# Rotary_Phone_Reader.net
KiCad netlist of a schematic drawn in EAGLE
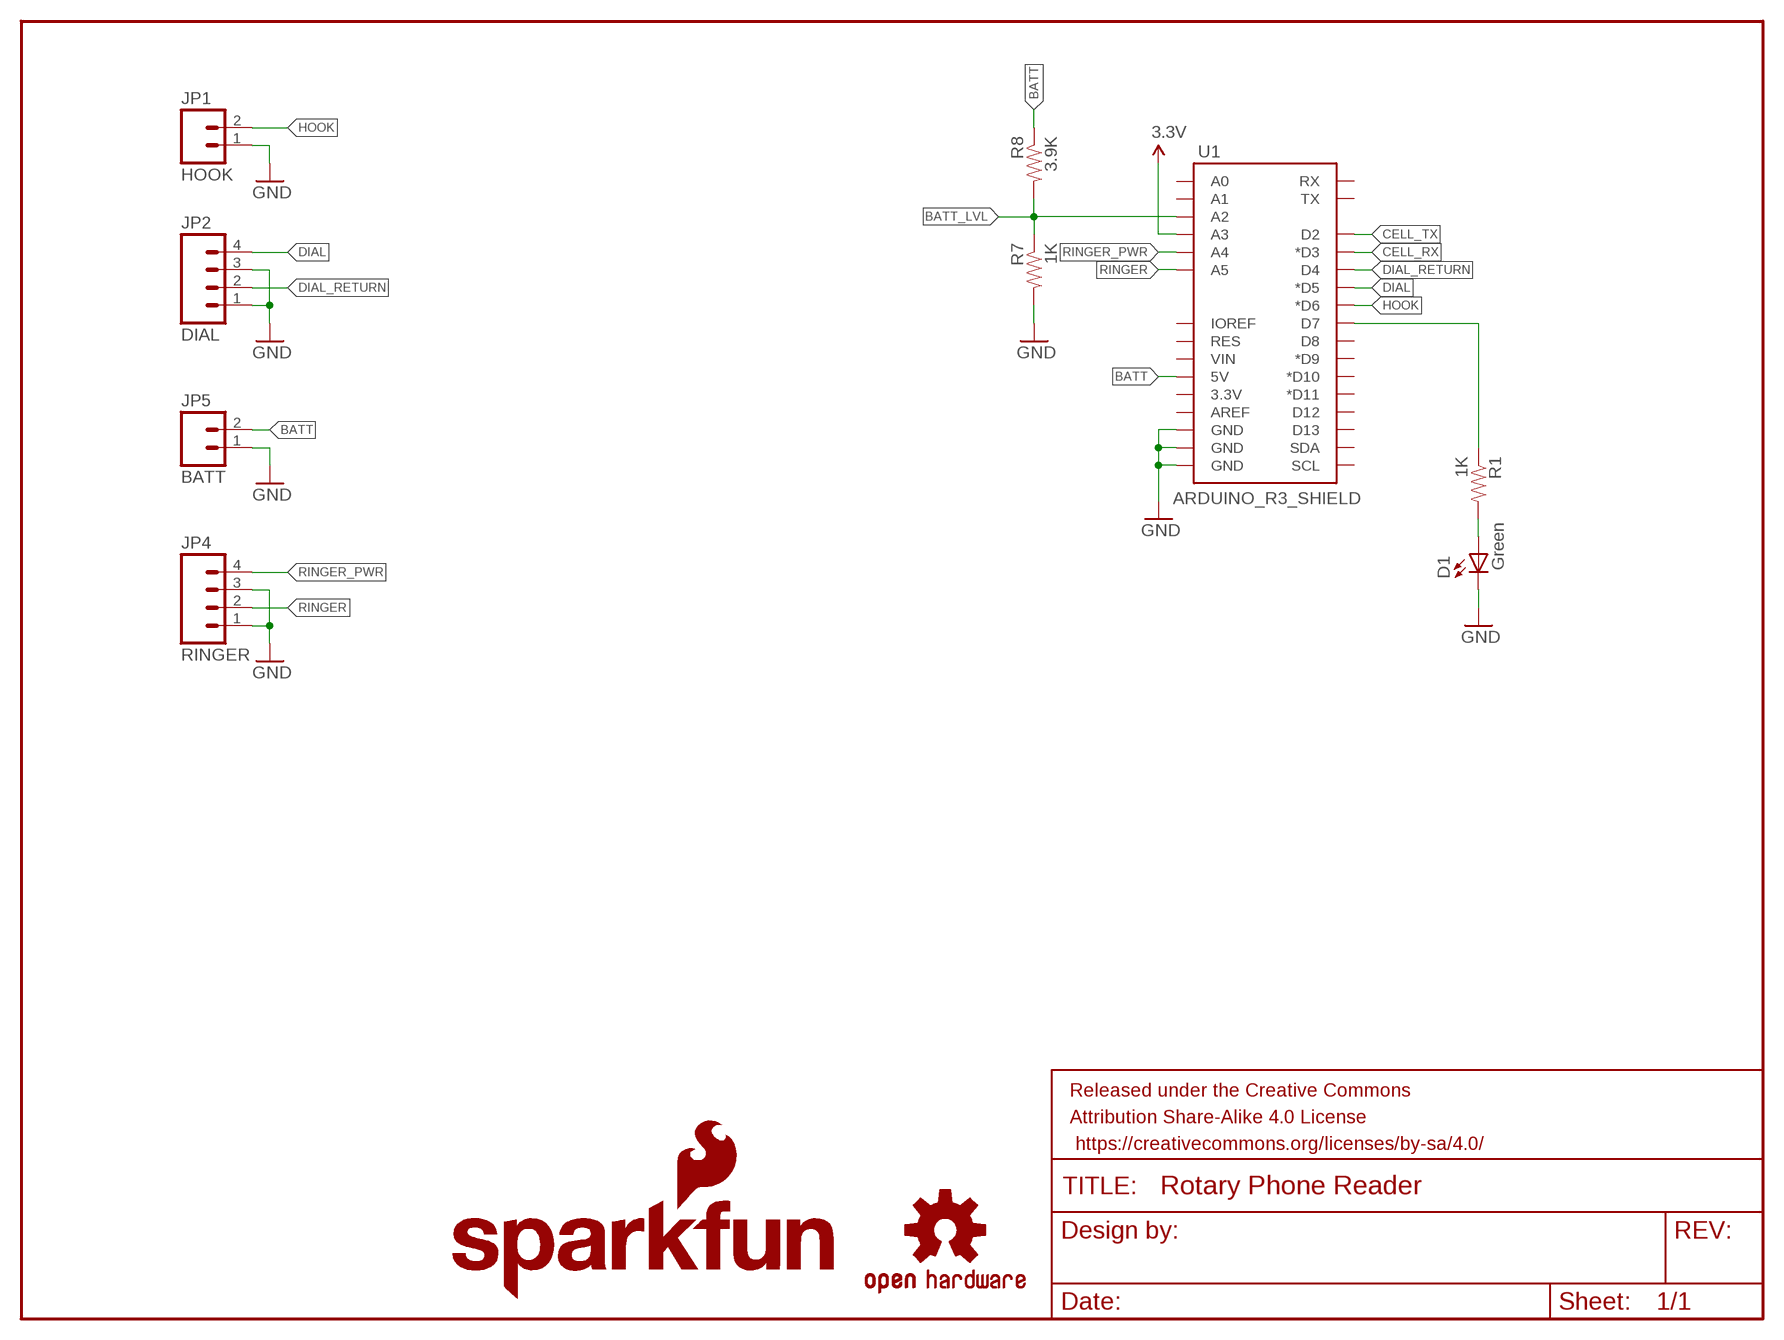
[diagram p0: schematic, sheet 1]

(export (version "E")
  (design (tool "Eeschema 10.0.6"))
  (components
    (comp (ref "D1")
      (value "Green")
      (footprint "eagle-import:LED5MM")
      (libsource (lib "eagle-import") (part "LED5MM"))
    )
    (comp (ref "FRAME1")
      (value "FRAME-LETTER")
      (footprint "eagle-import:CREATIVE_COMMONS")
      (libsource (lib "eagle-import") (part "FRAME-LETTER"))
    )
    (comp (ref "JP1")
      (value "HOOK")
      (footprint "eagle-import:JST-2-PTH")
      (libsource (lib "eagle-import") (part "M02JST-PTH-2"))
    )
    (comp (ref "JP2")
      (value "DIAL")
      (footprint "eagle-import:JST-4-PTH")
      (libsource (lib "eagle-import") (part "M04JST-PTH"))
    )
    (comp (ref "JP4")
      (value "RINGER")
      (footprint "eagle-import:JST-4-PTH")
      (libsource (lib "eagle-import") (part "M04JST-PTH"))
    )
    (comp (ref "JP5")
      (value "BATT")
      (footprint "eagle-import:JST-2-PTH")
      (libsource (lib "eagle-import") (part "M02JST-PTH-2"))
    )
    (comp (ref "LOGO1")
      (value "SFE_LOGO_NAME_FLAME.1_INCH")
      (footprint "eagle-import:SFE_LOGO_NAME_FLAME_.1")
      (libsource (lib "eagle-import") (part "SFE_LOGO_NAME_FLAME.1_INCH"))
    )
    (comp (ref "R1")
      (value "1K")
      (footprint "eagle-import:AXIAL-0.4")
      (libsource (lib "eagle-import") (part "RESISTORPTH-1/4W"))
    )
    (comp (ref "R7")
      (value "1K")
      (footprint "eagle-import:AXIAL-0.4")
      (libsource (lib "eagle-import") (part "RESISTORPTH-1/4W"))
    )
    (comp (ref "R8")
      (value "3.9K")
      (footprint "eagle-import:AXIAL-0.4")
      (libsource (lib "eagle-import") (part "RESISTORPTH-1/4W"))
    )
    (comp (ref "U$7")
      (value "OSHW-LOGOS")
      (footprint "eagle-import:OSHW-LOGO-S")
      (libsource (lib "eagle-import") (part "OSHW-LOGOS"))
    )
    (comp (ref "U1")
      (value "ARDUINO_R3_SHIELD")
      (footprint "eagle-import:UNO_R3_SHIELD")
      (libsource (lib "eagle-import") (part "ARDUINO_R3_SHIELD"))
    )
  )
  (nets
    (net (code "1") (name "3.3V") (class "Default")
      (node (ref "U1") (pin "A3") (pinfunction "A3_A3") (pintype "bidirectional"))
    )
    (net (code "2") (name "BATT") (class "Default")
      (node (ref "JP5") (pin "2") (pinfunction "2_2") (pintype "passive"))
      (node (ref "R8") (pin "P$1") (pinfunction "1_P$1") (pintype "passive"))
      (node (ref "U1") (pin "5V") (pinfunction "5V_5V") (pintype "bidirectional"))
    )
    (net (code "3") (name "BATT_LVL") (class "Default")
      (node (ref "R7") (pin "P$1") (pinfunction "1_P$1") (pintype "passive"))
      (node (ref "R8") (pin "P$2") (pinfunction "2_P$2") (pintype "passive"))
      (node (ref "U1") (pin "A2") (pinfunction "A2_A2") (pintype "bidirectional"))
    )
    (net (code "4") (name "CELL_RX") (class "Default")
      (node (ref "U1") (pin "D3") (pinfunction "*D3_D3") (pintype "bidirectional"))
    )
    (net (code "5") (name "CELL_TX") (class "Default")
      (node (ref "U1") (pin "D2") (pinfunction "D2_D2") (pintype "bidirectional"))
    )
    (net (code "6") (name "DIAL") (class "Default")
      (node (ref "JP2") (pin "4") (pinfunction "4_4") (pintype "passive"))
      (node (ref "U1") (pin "D5") (pinfunction "*D5_D5") (pintype "bidirectional"))
    )
    (net (code "7") (name "DIAL_RETURN") (class "Default")
      (node (ref "JP2") (pin "2") (pinfunction "2_2") (pintype "passive"))
      (node (ref "U1") (pin "D4") (pinfunction "D4_D4") (pintype "bidirectional"))
    )
    (net (code "8") (name "GND") (class "Default")
      (node (ref "D1") (pin "K") (pinfunction "C_K") (pintype "passive"))
      (node (ref "JP1") (pin "1") (pinfunction "1_1") (pintype "passive"))
      (node (ref "JP2") (pin "1") (pinfunction "1_1") (pintype "passive"))
      (node (ref "JP2") (pin "3") (pinfunction "3_3") (pintype "passive"))
      (node (ref "JP4") (pin "1") (pinfunction "1_1") (pintype "passive"))
      (node (ref "JP4") (pin "3") (pinfunction "3_3") (pintype "passive"))
      (node (ref "JP5") (pin "1") (pinfunction "1_1") (pintype "passive"))
      (node (ref "R7") (pin "P$2") (pinfunction "2_P$2") (pintype "passive"))
      (node (ref "U1") (pin "GND@0") (pinfunction "GND_GND@0") (pintype "bidirectional"))
      (node (ref "U1") (pin "GND@1") (pinfunction "GND_GND@1") (pintype "bidirectional"))
      (node (ref "U1") (pin "GND@2") (pinfunction "GND_GND@2") (pintype "bidirectional"))
    )
    (net (code "9") (name "HOOK") (class "Default")
      (node (ref "JP1") (pin "2") (pinfunction "2_2") (pintype "passive"))
      (node (ref "U1") (pin "D6") (pinfunction "*D6_D6") (pintype "bidirectional"))
    )
    (net (code "10") (name "Net-(R1-1)") (class "Default")
      (node (ref "R1") (pin "P$1") (pinfunction "1_P$1") (pintype "passive"))
      (node (ref "U1") (pin "D7") (pinfunction "D7_D7") (pintype "bidirectional"))
    )
    (net (code "11") (name "Net-(R1-2)") (class "Default")
      (node (ref "D1") (pin "A") (pinfunction "A_A") (pintype "passive"))
      (node (ref "R1") (pin "P$2") (pinfunction "2_P$2") (pintype "passive"))
    )
    (net (code "12") (name "RINGER") (class "Default")
      (node (ref "JP4") (pin "2") (pinfunction "2_2") (pintype "passive"))
      (node (ref "U1") (pin "A5") (pinfunction "A5_A5") (pintype "bidirectional"))
    )
    (net (code "13") (name "RINGER_PWR") (class "Default")
      (node (ref "JP4") (pin "4") (pinfunction "4_4") (pintype "passive"))
      (node (ref "U1") (pin "A4") (pinfunction "A4_A4") (pintype "bidirectional"))
    )
    (net (code "14") (name "unconnected-(U1-*D9-PadD9)") (class "Default")
      (node (ref "U1") (pin "D9") (pinfunction "*D9_D9") (pintype "bidirectional"))
    )
    (net (code "15") (name "unconnected-(U1-*D10-PadD10)") (class "Default")
      (node (ref "U1") (pin "D10") (pinfunction "*D10_D10") (pintype "bidirectional"))
    )
    (net (code "16") (name "unconnected-(U1-*D11-PadD11)") (class "Default")
      (node (ref "U1") (pin "D11") (pinfunction "*D11_D11") (pintype "bidirectional"))
    )
    (net (code "17") (name "unconnected-(U1-Pad3.3V)") (class "Default")
      (node (ref "U1") (pin "3.3V") (pinfunction "3.3V_3.3V") (pintype "bidirectional"))
    )
    (net (code "18") (name "unconnected-(U1-PadA0)") (class "Default")
      (node (ref "U1") (pin "A0") (pinfunction "A0_A0") (pintype "bidirectional"))
    )
    (net (code "19") (name "unconnected-(U1-PadA1)") (class "Default")
      (node (ref "U1") (pin "A1") (pinfunction "A1_A1") (pintype "bidirectional"))
    )
    (net (code "20") (name "unconnected-(U1-PadAREF)") (class "Default")
      (node (ref "U1") (pin "AREF") (pinfunction "AREF_AREF") (pintype "bidirectional"))
    )
    (net (code "21") (name "unconnected-(U1-PadD8)") (class "Default")
      (node (ref "U1") (pin "D8") (pinfunction "D8_D8") (pintype "bidirectional"))
    )
    (net (code "22") (name "unconnected-(U1-PadD12)") (class "Default")
      (node (ref "U1") (pin "D12") (pinfunction "D12_D12") (pintype "bidirectional"))
    )
    (net (code "23") (name "unconnected-(U1-PadD13)") (class "Default")
      (node (ref "U1") (pin "D13") (pinfunction "D13_D13") (pintype "bidirectional"))
    )
    (net (code "24") (name "unconnected-(U1-PadIOREF)") (class "Default")
      (node (ref "U1") (pin "IOREF") (pinfunction "IOREF_IOREF") (pintype "bidirectional"))
    )
    (net (code "25") (name "unconnected-(U1-PadRES)") (class "Default")
      (node (ref "U1") (pin "RES") (pinfunction "RES_RES") (pintype "bidirectional"))
    )
    (net (code "26") (name "unconnected-(U1-PadRX)") (class "Default")
      (node (ref "U1") (pin "RX") (pinfunction "RX_RX") (pintype "bidirectional"))
    )
    (net (code "27") (name "unconnected-(U1-PadSCL)") (class "Default")
      (node (ref "U1") (pin "SCL") (pinfunction "SCL_SCL") (pintype "bidirectional"))
    )
    (net (code "28") (name "unconnected-(U1-PadSDA)") (class "Default")
      (node (ref "U1") (pin "SDA") (pinfunction "SDA_SDA") (pintype "bidirectional"))
    )
    (net (code "29") (name "unconnected-(U1-PadTX)") (class "Default")
      (node (ref "U1") (pin "TX") (pinfunction "TX_TX") (pintype "bidirectional"))
    )
    (net (code "30") (name "unconnected-(U1-PadVIN)") (class "Default")
      (node (ref "U1") (pin "VIN") (pinfunction "VIN_VIN") (pintype "bidirectional"))
    )
  )
)
